# untitled.net
KiCad netlist of a schematic drawn in EAGLE
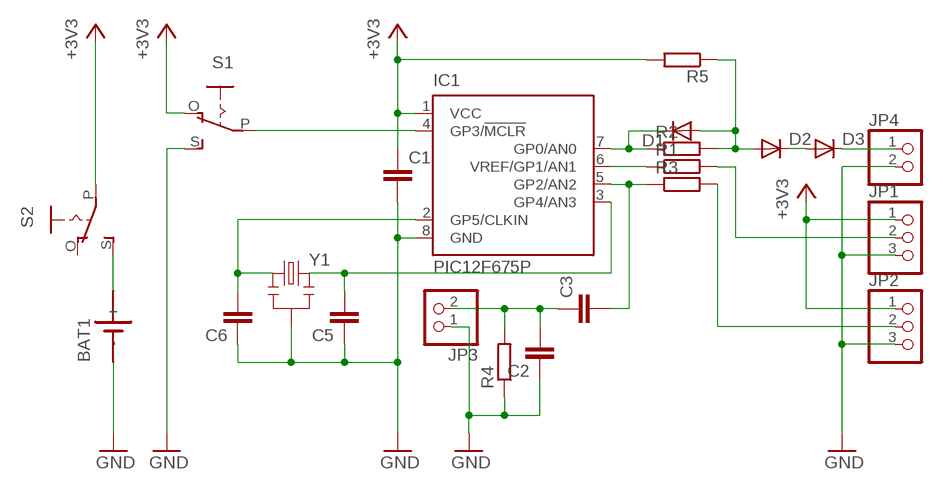
[diagram p0: schematic, sheet 1]

(export (version "E")
  (design (tool "Eeschema 10.0.6"))
  (components
    (comp (ref "BAT1")
      (value "SN2032")
      (footprint "eagle-import:SN2032")
      (libsource (lib "eagle-import") (part "SN2032"))
    )
    (comp (ref "C1")
      (value "C-EU025-025X050")
      (footprint "eagle-import:C025-025X050")
      (libsource (lib "eagle-import") (part "C-EU025-025X050"))
    )
    (comp (ref "C2")
      (value "C-EU025-025X050")
      (footprint "eagle-import:C025-025X050")
      (libsource (lib "eagle-import") (part "C-EU025-025X050"))
    )
    (comp (ref "C3")
      (value "C-EU025-025X050")
      (footprint "eagle-import:C025-025X050")
      (libsource (lib "eagle-import") (part "C-EU025-025X050"))
    )
    (comp (ref "C5")
      (value "C-EU025-025X050")
      (footprint "eagle-import:C025-025X050")
      (libsource (lib "eagle-import") (part "C-EU025-025X050"))
    )
    (comp (ref "C6")
      (value "C-EU025-025X050")
      (footprint "eagle-import:C025-025X050")
      (libsource (lib "eagle-import") (part "C-EU025-025X050"))
    )
    (comp (ref "D1")
      (value "DIODE-D-2.5")
      (footprint "eagle-import:D-2.5")
      (libsource (lib "eagle-import") (part "DIODE-D-2.5"))
    )
    (comp (ref "D2")
      (value "DIODE-D-2.5")
      (footprint "eagle-import:D-2.5")
      (libsource (lib "eagle-import") (part "DIODE-D-2.5"))
    )
    (comp (ref "D3")
      (value "DIODE-D-2.5")
      (footprint "eagle-import:D-2.5")
      (libsource (lib "eagle-import") (part "DIODE-D-2.5"))
    )
    (comp (ref "IC1")
      (value "PIC12F675P")
      (footprint "eagle-import:DIL8")
      (fields (field (name "MF") "MICROCHIP") (field (name "MPN") "PIC12F675-E/P"))
      (libsource (lib "eagle-import") (part "PIC12F675P"))
    )
    (comp (ref "JP1")
      (value "PINHD-1X3")
      (footprint "eagle-import:1X03")
      (libsource (lib "eagle-import") (part "PINHD-1X3"))
    )
    (comp (ref "JP2")
      (value "PINHD-1X3")
      (footprint "eagle-import:1X03")
      (libsource (lib "eagle-import") (part "PINHD-1X3"))
    )
    (comp (ref "JP3")
      (value "PINHD-1X2")
      (footprint "eagle-import:1X02")
      (libsource (lib "eagle-import") (part "PINHD-1X2"))
    )
    (comp (ref "JP4")
      (value "PINHD-1X2")
      (footprint "eagle-import:1X02")
      (libsource (lib "eagle-import") (part "PINHD-1X2"))
    )
    (comp (ref "R1")
      (value "R-EU_0204/2V")
      (footprint "eagle-import:0204V")
      (libsource (lib "eagle-import") (part "R-EU_0204/2V"))
    )
    (comp (ref "R2")
      (value "R-EU_0204/2V")
      (footprint "eagle-import:0204V")
      (libsource (lib "eagle-import") (part "R-EU_0204/2V"))
    )
    (comp (ref "R3")
      (value "R-EU_0204/2V")
      (footprint "eagle-import:0204V")
      (libsource (lib "eagle-import") (part "R-EU_0204/2V"))
    )
    (comp (ref "R4")
      (value "R-EU_0204/2V")
      (footprint "eagle-import:0204V")
      (libsource (lib "eagle-import") (part "R-EU_0204/2V"))
    )
    (comp (ref "R5")
      (value "R-EU_0204/2V")
      (footprint "eagle-import:0204V")
      (libsource (lib "eagle-import") (part "R-EU_0204/2V"))
    )
    (comp (ref "S1")
      (value "EG1218S")
      (footprint "eagle-import:EG1218")
      (libsource (lib "eagle-import") (part "EG1218S"))
    )
    (comp (ref "S2")
      (value "EG1218S")
      (footprint "eagle-import:EG1218")
      (libsource (lib "eagle-import") (part "EG1218S"))
    )
    (comp (ref "Y1")
      (value "RESONATORPTH")
      (footprint "eagle-import:RESONATOR-PTH")
      (libsource (lib "eagle-import") (part "RESONATORPTH"))
    )
  )
  (nets
    (net (code "1") (name "+3V3") (class "Default")
      (node (ref "C1") (pin "1") (pinfunction "1_1") (pintype "passive"))
      (node (ref "IC1") (pin "1") (pinfunction "VCC_1") (pintype "power_in"))
      (node (ref "JP1") (pin "1") (pinfunction "1_1") (pintype "passive"))
      (node (ref "JP2") (pin "1") (pinfunction "1_1") (pintype "passive"))
      (node (ref "R5") (pin "2") (pinfunction "2_2") (pintype "passive"))
      (node (ref "S1") (pin "O") (pinfunction "O_O") (pintype "passive"))
      (node (ref "S2") (pin "P") (pinfunction "P_P") (pintype "passive"))
    )
    (net (code "2") (name "GND") (class "Default")
      (node (ref "BAT1") (pin "-") (pinfunction "-_-") (pintype "passive"))
      (node (ref "C1") (pin "2") (pinfunction "2_2") (pintype "passive"))
      (node (ref "C2") (pin "1") (pinfunction "1_1") (pintype "passive"))
      (node (ref "C5") (pin "1") (pinfunction "1_1") (pintype "passive"))
      (node (ref "C6") (pin "1") (pinfunction "1_1") (pintype "passive"))
      (node (ref "IC1") (pin "8") (pinfunction "GND_8") (pintype "power_in"))
      (node (ref "JP1") (pin "3") (pinfunction "3_3") (pintype "passive"))
      (node (ref "JP2") (pin "3") (pinfunction "3_3") (pintype "passive"))
      (node (ref "JP3") (pin "1") (pinfunction "1_1") (pintype "passive"))
      (node (ref "JP4") (pin "2") (pinfunction "2_2") (pintype "passive"))
      (node (ref "R4") (pin "1") (pinfunction "1_1") (pintype "passive"))
      (node (ref "S1") (pin "S") (pinfunction "S_S") (pintype "passive"))
      (node (ref "Y1") (pin "2") (pinfunction "2_2") (pintype "passive"))
    )
    (net (code "3") (name "Net-(BAT1-Pad+)") (class "Default")
      (node (ref "BAT1") (pin "+") (pinfunction "+_+") (pintype "passive"))
      (node (ref "S2") (pin "S") (pinfunction "S_S") (pintype "passive"))
    )
    (net (code "4") (name "Net-(C2-Pad2)") (class "Default")
      (node (ref "C2") (pin "2") (pinfunction "2_2") (pintype "passive"))
      (node (ref "C3") (pin "1") (pinfunction "1_1") (pintype "passive"))
      (node (ref "JP3") (pin "2") (pinfunction "2_2") (pintype "passive"))
      (node (ref "R4") (pin "2") (pinfunction "2_2") (pintype "passive"))
    )
    (net (code "5") (name "Net-(D1-PadA)") (class "Default")
      (node (ref "D1") (pin "A") (pinfunction "A_A") (pintype "passive"))
      (node (ref "D2") (pin "A") (pinfunction "A_A") (pintype "passive"))
      (node (ref "R2") (pin "2") (pinfunction "2_2") (pintype "passive"))
      (node (ref "R5") (pin "1") (pinfunction "1_1") (pintype "passive"))
    )
    (net (code "6") (name "Net-(D2-PadC)") (class "Default")
      (node (ref "D2") (pin "C") (pinfunction "C_C") (pintype "passive"))
      (node (ref "D3") (pin "A") (pinfunction "A_A") (pintype "passive"))
    )
    (net (code "7") (name "Net-(D3-PadC)") (class "Default")
      (node (ref "D3") (pin "C") (pinfunction "C_C") (pintype "passive"))
      (node (ref "JP4") (pin "1") (pinfunction "1_1") (pintype "passive"))
    )
    (net (code "8") (name "Net-(IC1-GP0{slash}AN0)") (class "Default")
      (node (ref "D1") (pin "C") (pinfunction "C_C") (pintype "passive"))
      (node (ref "IC1") (pin "7") (pinfunction "GP0/AN0_7") (pintype "bidirectional"))
      (node (ref "R2") (pin "1") (pinfunction "1_1") (pintype "passive"))
    )
    (net (code "9") (name "Net-(IC1-GP2{slash}AN2)") (class "Default")
      (node (ref "C3") (pin "2") (pinfunction "2_2") (pintype "passive"))
      (node (ref "IC1") (pin "5") (pinfunction "GP2/AN2_5") (pintype "bidirectional"))
      (node (ref "R3") (pin "1") (pinfunction "1_1") (pintype "passive"))
    )
    (net (code "10") (name "Net-(IC1-GP3{slash}~{MCLR})") (class "Default")
      (node (ref "IC1") (pin "4") (pinfunction "GP3/~{MCLR}_4") (pintype "input"))
      (node (ref "S1") (pin "P") (pinfunction "P_P") (pintype "passive"))
    )
    (net (code "11") (name "Net-(IC1-GP4{slash}AN3)") (class "Default")
      (node (ref "C5") (pin "2") (pinfunction "2_2") (pintype "passive"))
      (node (ref "IC1") (pin "3") (pinfunction "GP4/AN3_3") (pintype "bidirectional"))
      (node (ref "Y1") (pin "3") (pinfunction "3_3") (pintype "passive"))
    )
    (net (code "12") (name "Net-(IC1-GP5{slash}CLKIN)") (class "Default")
      (node (ref "C6") (pin "2") (pinfunction "2_2") (pintype "passive"))
      (node (ref "IC1") (pin "2") (pinfunction "GP5/CLKIN_2") (pintype "bidirectional"))
      (node (ref "Y1") (pin "1") (pinfunction "1_1") (pintype "passive"))
    )
    (net (code "13") (name "Net-(IC1-VREF{slash}GP1{slash}AN1)") (class "Default")
      (node (ref "IC1") (pin "6") (pinfunction "VREF/GP1/AN1_6") (pintype "bidirectional"))
      (node (ref "R1") (pin "1") (pinfunction "1_1") (pintype "passive"))
    )
    (net (code "14") (name "Net-(JP1-Pad2)") (class "Default")
      (node (ref "JP1") (pin "2") (pinfunction "2_2") (pintype "passive"))
      (node (ref "R1") (pin "2") (pinfunction "2_2") (pintype "passive"))
    )
    (net (code "15") (name "Net-(JP2-Pad2)") (class "Default")
      (node (ref "JP2") (pin "2") (pinfunction "2_2") (pintype "passive"))
      (node (ref "R3") (pin "2") (pinfunction "2_2") (pintype "passive"))
    )
    (net (code "16") (name "unconnected-(S2-PadO)") (class "Default")
      (node (ref "S2") (pin "O") (pinfunction "O_O") (pintype "passive"))
    )
  )
)
